# level_shifter-v10.net
KiCad netlist of a schematic drawn in EAGLE
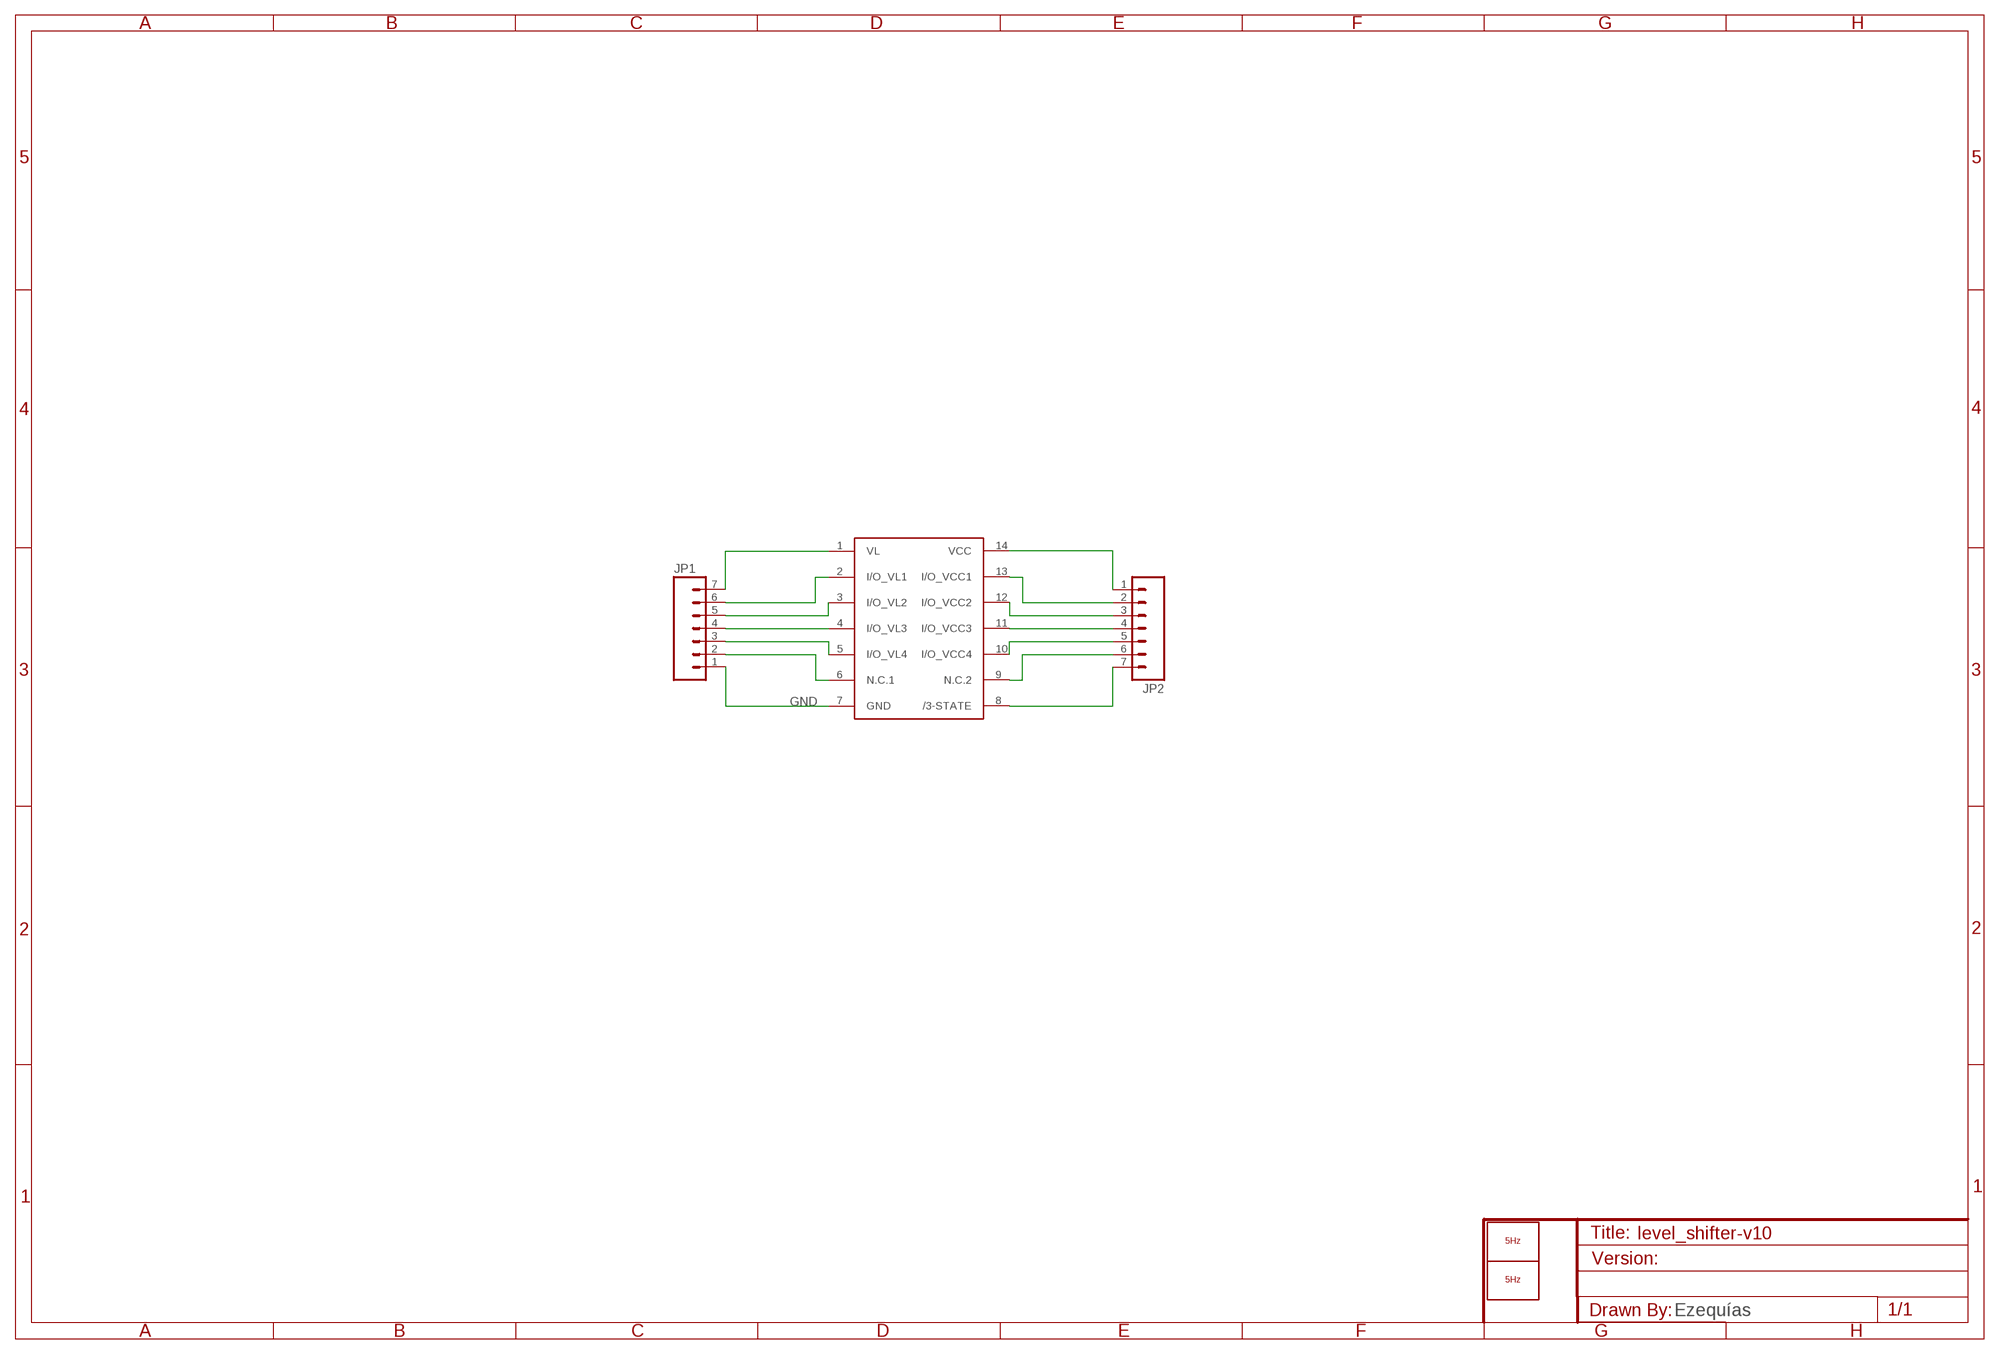
[diagram p0: schematic, sheet 1]

(export (version "E")
  (design (tool "Eeschema 10.0.6"))
  (components
    (comp (ref "JP1")
      (value "M07")
      (footprint "eagle-import:1X07")
      (libsource (lib "eagle-import") (part "M07"))
    )
    (comp (ref "JP2")
      (value "M07")
      (footprint "eagle-import:1X07")
      (libsource (lib "eagle-import") (part "M07"))
    )
    (comp (ref "LOGO1")
      (value "LOGO_5HZ_H_COOPER_15MM")
      (footprint "eagle-import:5HZ_LOGO_H_COOPER_15MM")
      (libsource (lib "eagle-import") (part "LOGO_5HZ_H_COOPER_15MM"))
    )
    (comp (ref "LOGO2")
      (value "LOGO_5HZ_MAIN_5MM")
      (footprint "eagle-import:5HZ_LOGO_MAIN_5MM")
      (libsource (lib "eagle-import") (part "LOGO_5HZ_MAIN_5MM"))
    )
    (comp (ref "U$1")
      (value "MAX3378")
      (footprint "eagle-import:TSSOP14")
      (libsource (lib "eagle-import") (part "MAX3378"))
    )
  )
  (nets
    (net (code "1") (name "/GND") (class "Default")
      (node (ref "JP1") (pin "1") (pinfunction "1_1") (pintype "passive"))
      (node (ref "U$1") (pin "7") (pinfunction "GND_7") (pintype "bidirectional"))
    )
    (net (code "2") (name "Net-(U$1-I{slash}O_VCC1)") (class "Default")
      (node (ref "JP2") (pin "2") (pinfunction "2_2") (pintype "passive"))
      (node (ref "U$1") (pin "13") (pinfunction "I/O_VCC1_13") (pintype "bidirectional"))
    )
    (net (code "3") (name "Net-(U$1-I{slash}O_VCC2)") (class "Default")
      (node (ref "JP2") (pin "3") (pinfunction "3_3") (pintype "passive"))
      (node (ref "U$1") (pin "12") (pinfunction "I/O_VCC2_12") (pintype "bidirectional"))
    )
    (net (code "4") (name "Net-(U$1-I{slash}O_VCC3)") (class "Default")
      (node (ref "JP2") (pin "4") (pinfunction "4_4") (pintype "passive"))
      (node (ref "U$1") (pin "11") (pinfunction "I/O_VCC3_11") (pintype "bidirectional"))
    )
    (net (code "5") (name "Net-(U$1-I{slash}O_VCC4)") (class "Default")
      (node (ref "JP2") (pin "5") (pinfunction "5_5") (pintype "passive"))
      (node (ref "U$1") (pin "10") (pinfunction "I/O_VCC4_10") (pintype "bidirectional"))
    )
    (net (code "6") (name "Net-(U$1-I{slash}O_VL1)") (class "Default")
      (node (ref "JP1") (pin "6") (pinfunction "6_6") (pintype "passive"))
      (node (ref "U$1") (pin "2") (pinfunction "I/O_VL1_2") (pintype "bidirectional"))
    )
    (net (code "7") (name "Net-(U$1-I{slash}O_VL2)") (class "Default")
      (node (ref "JP1") (pin "5") (pinfunction "5_5") (pintype "passive"))
      (node (ref "U$1") (pin "3") (pinfunction "I/O_VL2_3") (pintype "bidirectional"))
    )
    (net (code "8") (name "Net-(U$1-I{slash}O_VL3)") (class "Default")
      (node (ref "JP1") (pin "4") (pinfunction "4_4") (pintype "passive"))
      (node (ref "U$1") (pin "4") (pinfunction "I/O_VL3_4") (pintype "bidirectional"))
    )
    (net (code "9") (name "Net-(U$1-I{slash}O_VL4)") (class "Default")
      (node (ref "JP1") (pin "3") (pinfunction "3_3") (pintype "passive"))
      (node (ref "U$1") (pin "5") (pinfunction "I/O_VL4_5") (pintype "bidirectional"))
    )
    (net (code "10") (name "Net-(U$1-N.C.1)") (class "Default")
      (node (ref "JP1") (pin "2") (pinfunction "2_2") (pintype "passive"))
      (node (ref "U$1") (pin "6") (pinfunction "N.C.1_6") (pintype "bidirectional"))
    )
    (net (code "11") (name "Net-(U$1-N.C.2)") (class "Default")
      (node (ref "JP2") (pin "6") (pinfunction "6_6") (pintype "passive"))
      (node (ref "U$1") (pin "9") (pinfunction "N.C.2_9") (pintype "bidirectional"))
    )
    (net (code "12") (name "Net-(U$1-VCC)") (class "Default")
      (node (ref "JP2") (pin "1") (pinfunction "1_1") (pintype "passive"))
      (node (ref "U$1") (pin "14") (pinfunction "VCC_14") (pintype "bidirectional"))
    )
    (net (code "13") (name "Net-(U$1-VL)") (class "Default")
      (node (ref "JP1") (pin "7") (pinfunction "7_7") (pintype "passive"))
      (node (ref "U$1") (pin "1") (pinfunction "VL_1") (pintype "bidirectional"))
    )
    (net (code "14") (name "Net-(U$1-{slash}3-STATE)") (class "Default")
      (node (ref "JP2") (pin "7") (pinfunction "7_7") (pintype "passive"))
      (node (ref "U$1") (pin "8") (pinfunction "/3-STATE_8") (pintype "bidirectional"))
    )
  )
)
